# ERBB.net
KiCad netlist of a schematic drawn in Altium Designer
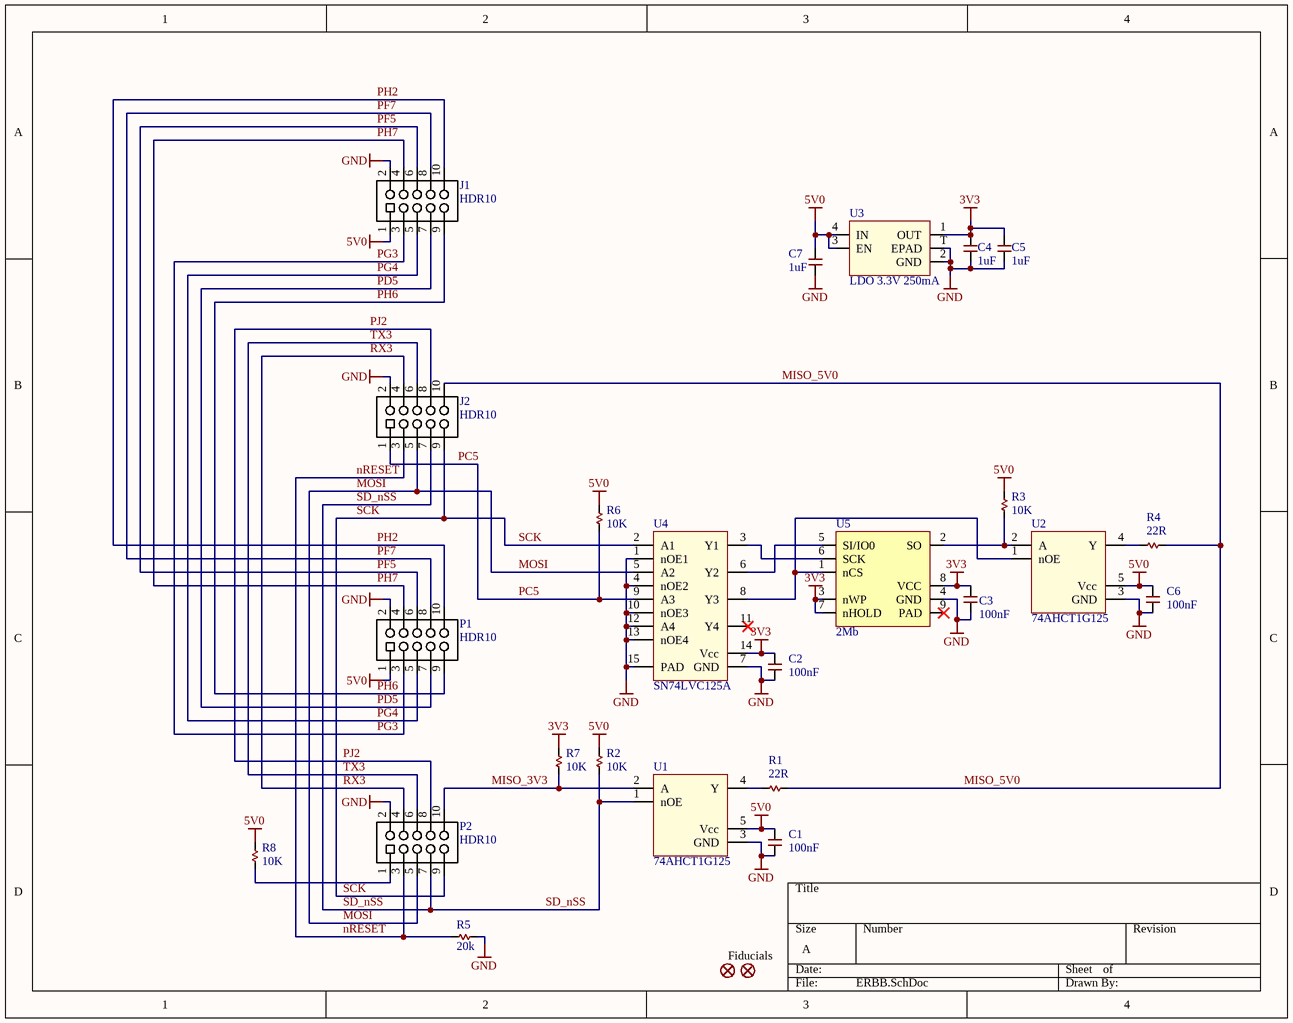
[diagram p0: ERBB.SchDoc]

(export (version "E")
  (design (tool "Eeschema 10.0.6"))
  (components
    (comp (ref "C1")
      (value "100nF")
      (footprint "C0402")
      (description "CAP CER 0402 100nF 16V 10% X7R")
      (fields (field (name "MANUFACTURER") "Murata") (field (name "PART") "0.1uF 16V X7R 0402"))
      (libsource (lib "Capacitors") (part "100nF 0402 16V X7R"))
    )
    (comp (ref "C2")
      (value "100nF")
      (footprint "C0402")
      (description "CAP CER 0402 100nF 16V 10% X7R")
      (fields (field (name "MANUFACTURER") "Murata") (field (name "PART") "0.1uF 16V X7R 0402"))
      (libsource (lib "Capacitors") (part "100nF 0402 16V X7R"))
    )
    (comp (ref "C3")
      (value "100nF")
      (footprint "C0402")
      (description "CAP CER 0402 100nF 16V 10% X7R")
      (fields (field (name "MANUFACTURER") "Murata") (field (name "PART") "0.1uF 16V X7R 0402"))
      (libsource (lib "Capacitors") (part "100nF 0402 16V X7R"))
    )
    (comp (ref "C4")
      (value "1uF")
      (footprint "C0402")
      (description "CAP CER 0402 1uF 6.3V 10% X5R")
      (fields (field (name "MANUFACTURER") "Murata") (field (name "PART") "1uF 6.3V X5R 0402"))
      (libsource (lib "Capacitors") (part "1uF 0402 6.3V X5R"))
    )
    (comp (ref "C5")
      (value "1uF")
      (footprint "C0402")
      (description "CAP CER 0402 1uF 6.3V 10% X5R")
      (fields (field (name "MANUFACTURER") "Murata") (field (name "PART") "1uF 6.3V X5R 0402"))
      (libsource (lib "Capacitors") (part "1uF 0402 6.3V X5R"))
    )
    (comp (ref "C6")
      (value "100nF")
      (footprint "C0402")
      (description "CAP CER 0402 100nF 16V 10% X7R")
      (fields (field (name "MANUFACTURER") "Murata") (field (name "PART") "0.1uF 16V X7R 0402"))
      (libsource (lib "Capacitors") (part "100nF 0402 16V X7R"))
    )
    (comp (ref "C7")
      (value "1uF")
      (footprint "C0402")
      (description "CAP CER 0402 1uF 6.3V 10% X5R")
      (fields (field (name "MANUFACTURER") "Murata") (field (name "PART") "1uF 6.3V X5R 0402"))
      (libsource (lib "Capacitors") (part "1uF 0402 6.3V X5R"))
    )
    (comp (ref "FID1")
      (value "FIDUCIAL")
      (footprint "FIDUCIAL-1X2")
      (description "Fiducial")
      (libsource (lib "3Delight") (part "FIDUCIAL"))
    )
    (comp (ref "FID2")
      (value "FIDUCIAL")
      (footprint "FIDUCIAL-1X2")
      (description "Fiducial")
      (libsource (lib "3Delight") (part "FIDUCIAL"))
    )
    (comp (ref "J1")
      (value "HDR10")
      (footprint "HDR2X5_PLUG")
      (description "CONN FM HEADER VERT 10POS GOLD")
      (fields (field (name "MANUFACTURER") "Multicomp") (field (name "TOLERANCE") "-NA-"))
      (libsource (lib "Connectors") (part "Header FM 10PIN 2ROW T-HOLE VERT"))
    )
    (comp (ref "J2")
      (value "HDR10")
      (footprint "HDR2X5_PLUG")
      (description "CONN FM HEADER VERT 10POS GOLD")
      (fields (field (name "MANUFACTURER") "Multicomp") (field (name "TOLERANCE") "-NA-"))
      (libsource (lib "Connectors") (part "Header FM 10PIN 2ROW T-HOLE VERT"))
    )
    (comp (ref "P1")
      (value "HDR10")
      (footprint "HDR2X5 IDC")
      (description "CONN HEADER VERT 10POS GOLD")
      (fields (field (name "MANUFACTURER") "On Shore") (field (name "TOLERANCE") "-NA-"))
      (libsource (lib "Connectors") (part "Header 10PIN 2ROW T-HOLE VERT SHROUDED"))
    )
    (comp (ref "P2")
      (value "HDR10")
      (footprint "HDR2X5 IDC")
      (description "CONN HEADER VERT 10POS GOLD")
      (fields (field (name "MANUFACTURER") "On Shore") (field (name "TOLERANCE") "-NA-"))
      (libsource (lib "Connectors") (part "Header 10PIN 2ROW T-HOLE VERT SHROUDED"))
    )
    (comp (ref "R1")
      (value "22R")
      (footprint "R0402")
      (description "RES 0402 22r 62.5mW 1%")
      (fields (field (name "MANUFACTURER") "Yageo") (field (name "TOLERANCE") "+/- 1%"))
      (libsource (lib "Resistors") (part "22R 1% 0402"))
    )
    (comp (ref "R2")
      (value "10K")
      (footprint "R0402")
      (description "RES SMD 10K OHM 1% 1/16W 0402")
      (fields (field (name "MANUFACTURER") "Yageo") (field (name "PART") "10k 1% 0402"))
      (libsource (lib "Resistors") (part "10k 1% 0402"))
    )
    (comp (ref "R3")
      (value "10K")
      (footprint "R0402")
      (description "RES SMD 10K OHM 1% 1/16W 0402")
      (fields (field (name "MANUFACTURER") "Yageo") (field (name "PART") "10k 1% 0402"))
      (libsource (lib "Resistors") (part "10k 1% 0402"))
    )
    (comp (ref "R4")
      (value "22R")
      (footprint "R0402")
      (description "RES 0402 22r 62.5mW 1%")
      (fields (field (name "MANUFACTURER") "Yageo") (field (name "TOLERANCE") "+/- 1%"))
      (libsource (lib "Resistors") (part "22R 1% 0402"))
    )
    (comp (ref "R5")
      (value "20k")
      (footprint "R0402")
      (description "RES SMD 20K OHM 1% 1/16W 0402")
      (fields (field (name "MANUFACTURER") "Yageo") (field (name "TOLERANCE") "1%"))
      (libsource (lib "Resistors") (part "20k 1% 0402"))
    )
    (comp (ref "R6")
      (value "10K")
      (footprint "R0402")
      (description "RES SMD 10K OHM 1% 1/16W 0402")
      (fields (field (name "MANUFACTURER") "Yageo") (field (name "PART") "10k 1% 0402"))
      (libsource (lib "Resistors") (part "10k 1% 0402"))
    )
    (comp (ref "R7")
      (value "10K")
      (footprint "R0402")
      (description "RES SMD 10K OHM 1% 1/16W 0402")
      (fields (field (name "MANUFACTURER") "Yageo") (field (name "PART") "10k 1% 0402"))
      (libsource (lib "Resistors") (part "10k 1% 0402"))
    )
    (comp (ref "R8")
      (value "10K")
      (footprint "R0402")
      (description "RES SMD 10K OHM 1% 1/16W 0402")
      (fields (field (name "MANUFACTURER") "Yageo") (field (name "PART") "10k 1% 0402"))
      (libsource (lib "Resistors") (part "10k 1% 0402"))
    )
    (comp (ref "U1")
      (value "74AHCT1G125")
      (footprint "SOTFL50P160X60-5L")
      (description "IC BUS BUFF TRI-ST N-INV  SOT-553")
      (fields (field (name "TOLERANCE") "-NA-") (field (name "MANUFACTURER") "TI"))
      (libsource (lib "ICs-Logic") (part "SN74AHCT1G125DRLR"))
    )
    (comp (ref "U2")
      (value "74AHCT1G125")
      (footprint "SOTFL50P160X60-5L")
      (description "IC BUS BUFF TRI-ST N-INV  SOT-553")
      (fields (field (name "TOLERANCE") "-NA-") (field (name "MANUFACTURER") "TI"))
      (libsource (lib "ICs-Logic") (part "SN74AHCT1G125DRLR"))
    )
    (comp (ref "U3")
      (value "LDO 3.3V 250mA")
      (footprint "XDFN4 1X1")
      (description "IC REG LINEAR 3.3V 250MA 4XDFN")
      (fields (field (name "MANUFACTURER") "On Semi") (field (name "TOLERANCE") "-NA-"))
      (libsource (lib "ICs-Power") (part "LDO 3.3V 250mA"))
    )
    (comp (ref "U4")
      (value "SN74LVC125A")
      (footprint "PVQFN14_3.5X3.5")
      (description "IC BUS BUFF TRI-ST QD 14VQFN")
      (fields (field (name "TOLERANCE") "-NA-") (field (name "MANUFACTURER") "TI"))
      (libsource (lib "ICs-Logic") (part "SN74LVC125A"))
    )
    (comp (ref "U5")
      (value "2Mb")
      (footprint "USON8 2X3")
      (description "IC FLASH 2MBIT 104MHZ 8USON")
      (fields (field (name "MANUFACTURER") "Winbond") (field (name "TOLERANCE") "-NA-"))
      (libsource (lib "ICs-uC") (part "W25X20CL"))
    )
  )
  (nets
    (net (code "1") (name "/MISO_3V3") (class "Default")
      (node (ref "P2") (pin "10") (pinfunction "10_10") (pintype "passive"))
      (node (ref "R7") (pin "2") (pinfunction "2_2") (pintype "passive"))
      (node (ref "U1") (pin "2") (pinfunction "A_2") (pintype "passive"))
    )
    (net (code "2") (name "/MISO_5V0") (class "Default")
      (node (ref "J2") (pin "10") (pinfunction "10_10") (pintype "passive"))
      (node (ref "R1") (pin "2") (pinfunction "2_2") (pintype "passive"))
      (node (ref "R4") (pin "2") (pinfunction "2_2") (pintype "passive"))
    )
    (net (code "3") (name "/MOSI") (class "Default")
      (node (ref "J2") (pin "5") (pinfunction "5_5") (pintype "passive"))
      (node (ref "P2") (pin "5") (pinfunction "5_5") (pintype "passive"))
      (node (ref "U4") (pin "5") (pinfunction "A2_5") (pintype "passive"))
    )
    (net (code "4") (name "/PC5") (class "Default")
      (node (ref "J2") (pin "1") (pinfunction "1_1") (pintype "passive"))
      (node (ref "R6") (pin "2") (pinfunction "2_2") (pintype "passive"))
      (node (ref "U4") (pin "9") (pinfunction "A3_9") (pintype "passive"))
    )
    (net (code "5") (name "/PD5") (class "Default")
      (node (ref "J1") (pin "7") (pinfunction "7_7") (pintype "passive"))
      (node (ref "P1") (pin "7") (pinfunction "7_7") (pintype "passive"))
    )
    (net (code "6") (name "/PF5") (class "Default")
      (node (ref "J1") (pin "6") (pinfunction "6_6") (pintype "passive"))
      (node (ref "P1") (pin "6") (pinfunction "6_6") (pintype "passive"))
    )
    (net (code "7") (name "/PF7") (class "Default")
      (node (ref "J1") (pin "8") (pinfunction "8_8") (pintype "passive"))
      (node (ref "P1") (pin "8") (pinfunction "8_8") (pintype "passive"))
    )
    (net (code "8") (name "/PG3") (class "Default")
      (node (ref "J1") (pin "3") (pinfunction "3_3") (pintype "passive"))
      (node (ref "P1") (pin "3") (pinfunction "3_3") (pintype "passive"))
    )
    (net (code "9") (name "/PG4") (class "Default")
      (node (ref "J1") (pin "5") (pinfunction "5_5") (pintype "passive"))
      (node (ref "P1") (pin "5") (pinfunction "5_5") (pintype "passive"))
    )
    (net (code "10") (name "/PH2") (class "Default")
      (node (ref "J1") (pin "10") (pinfunction "10_10") (pintype "passive"))
      (node (ref "P1") (pin "10") (pinfunction "10_10") (pintype "passive"))
    )
    (net (code "11") (name "/PH6") (class "Default")
      (node (ref "J1") (pin "9") (pinfunction "9_9") (pintype "passive"))
      (node (ref "P1") (pin "9") (pinfunction "9_9") (pintype "passive"))
    )
    (net (code "12") (name "/PH7") (class "Default")
      (node (ref "J1") (pin "4") (pinfunction "4_4") (pintype "passive"))
      (node (ref "P1") (pin "4") (pinfunction "4_4") (pintype "passive"))
    )
    (net (code "13") (name "/PJ2") (class "Default")
      (node (ref "J2") (pin "8") (pinfunction "8_8") (pintype "passive"))
      (node (ref "P2") (pin "8") (pinfunction "8_8") (pintype "passive"))
    )
    (net (code "14") (name "/RX3") (class "Default")
      (node (ref "J2") (pin "4") (pinfunction "4_4") (pintype "passive"))
      (node (ref "P2") (pin "4") (pinfunction "4_4") (pintype "passive"))
    )
    (net (code "15") (name "/SCK") (class "Default")
      (node (ref "J2") (pin "9") (pinfunction "9_9") (pintype "passive"))
      (node (ref "P2") (pin "9") (pinfunction "9_9") (pintype "passive"))
      (node (ref "U4") (pin "2") (pinfunction "A1_2") (pintype "passive"))
    )
    (net (code "16") (name "/SD_nSS") (class "Default")
      (node (ref "J2") (pin "7") (pinfunction "7_7") (pintype "passive"))
      (node (ref "P2") (pin "7") (pinfunction "7_7") (pintype "passive"))
      (node (ref "R2") (pin "2") (pinfunction "2_2") (pintype "passive"))
      (node (ref "U1") (pin "1") (pinfunction "nOE_1") (pintype "passive"))
    )
    (net (code "17") (name "/TX3") (class "Default")
      (node (ref "J2") (pin "6") (pinfunction "6_6") (pintype "passive"))
      (node (ref "P2") (pin "6") (pinfunction "6_6") (pintype "passive"))
    )
    (net (code "18") (name "/nRESET") (class "Default")
      (node (ref "J2") (pin "3") (pinfunction "3_3") (pintype "passive"))
      (node (ref "P2") (pin "3") (pinfunction "3_3") (pintype "passive"))
      (node (ref "R5") (pin "1") (pinfunction "1_1") (pintype "passive"))
    )
    (net (code "19") (name "3V3") (class "Default")
      (node (ref "C2") (pin "1") (pinfunction "1_1") (pintype "passive"))
      (node (ref "C3") (pin "2") (pinfunction "2_2") (pintype "passive"))
      (node (ref "C4") (pin "2") (pinfunction "2_2") (pintype "passive"))
      (node (ref "C5") (pin "2") (pinfunction "2_2") (pintype "passive"))
      (node (ref "R7") (pin "1") (pinfunction "1_1") (pintype "passive"))
      (node (ref "U3") (pin "1") (pinfunction "OUT_1") (pintype "power_in"))
      (node (ref "U4") (pin "14") (pinfunction "Vcc_14") (pintype "passive"))
      (node (ref "U5") (pin "3") (pinfunction "nWP_3") (pintype "passive"))
      (node (ref "U5") (pin "7") (pinfunction "nHOLD_7") (pintype "passive"))
      (node (ref "U5") (pin "8") (pinfunction "VCC_8") (pintype "passive"))
    )
    (net (code "20") (name "5V0") (class "Default")
      (node (ref "C1") (pin "2") (pinfunction "2_2") (pintype "passive"))
      (node (ref "C6") (pin "2") (pinfunction "2_2") (pintype "passive"))
      (node (ref "C7") (pin "2") (pinfunction "2_2") (pintype "passive"))
      (node (ref "J1") (pin "1") (pinfunction "1_1") (pintype "passive"))
      (node (ref "P1") (pin "1") (pinfunction "1_1") (pintype "passive"))
      (node (ref "R2") (pin "1") (pinfunction "1_1") (pintype "passive"))
      (node (ref "R3") (pin "1") (pinfunction "1_1") (pintype "passive"))
      (node (ref "R6") (pin "1") (pinfunction "1_1") (pintype "passive"))
      (node (ref "R8") (pin "1") (pinfunction "1_1") (pintype "passive"))
      (node (ref "U1") (pin "5") (pinfunction "Vcc_5") (pintype "passive"))
      (node (ref "U2") (pin "5") (pinfunction "Vcc_5") (pintype "passive"))
      (node (ref "U3") (pin "3") (pinfunction "EN_3") (pintype "power_in"))
      (node (ref "U3") (pin "4") (pinfunction "IN_4") (pintype "power_in"))
    )
    (net (code "21") (name "GND") (class "Default")
      (node (ref "C1") (pin "1") (pinfunction "1_1") (pintype "passive"))
      (node (ref "C2") (pin "2") (pinfunction "2_2") (pintype "passive"))
      (node (ref "C3") (pin "1") (pinfunction "1_1") (pintype "passive"))
      (node (ref "C4") (pin "1") (pinfunction "1_1") (pintype "passive"))
      (node (ref "C5") (pin "1") (pinfunction "1_1") (pintype "passive"))
      (node (ref "C6") (pin "1") (pinfunction "1_1") (pintype "passive"))
      (node (ref "C7") (pin "1") (pinfunction "1_1") (pintype "passive"))
      (node (ref "J1") (pin "2") (pinfunction "2_2") (pintype "passive"))
      (node (ref "J2") (pin "2") (pinfunction "2_2") (pintype "passive"))
      (node (ref "P1") (pin "2") (pinfunction "2_2") (pintype "passive"))
      (node (ref "P2") (pin "2") (pinfunction "2_2") (pintype "passive"))
      (node (ref "R5") (pin "2") (pinfunction "2_2") (pintype "passive"))
      (node (ref "U1") (pin "3") (pinfunction "GND_3") (pintype "passive"))
      (node (ref "U2") (pin "3") (pinfunction "GND_3") (pintype "passive"))
      (node (ref "U3") (pin "2") (pinfunction "GND_2") (pintype "power_in"))
      (node (ref "U3") (pin "T") (pinfunction "EPAD_T") (pintype "power_in"))
      (node (ref "U4") (pin "1") (pinfunction "nOE1_1") (pintype "passive"))
      (node (ref "U4") (pin "10") (pinfunction "nOE3_10") (pintype "passive"))
      (node (ref "U4") (pin "12") (pinfunction "A4_12") (pintype "passive"))
      (node (ref "U4") (pin "13") (pinfunction "nOE4_13") (pintype "passive"))
      (node (ref "U4") (pin "15") (pinfunction "PAD_15") (pintype "passive"))
      (node (ref "U4") (pin "4") (pinfunction "nOE2_4") (pintype "passive"))
      (node (ref "U4") (pin "7") (pinfunction "GND_7") (pintype "passive"))
      (node (ref "U5") (pin "4") (pinfunction "GND_4") (pintype "passive"))
    )
    (net (code "22") (name "Net-(P2-Pad1)") (class "Default")
      (node (ref "P2") (pin "1") (pinfunction "1_1") (pintype "passive"))
      (node (ref "R8") (pin "2") (pinfunction "2_2") (pintype "passive"))
    )
    (net (code "23") (name "Net-(U1-Y)") (class "Default")
      (node (ref "R1") (pin "1") (pinfunction "1_1") (pintype "passive"))
      (node (ref "U1") (pin "4") (pinfunction "Y_4") (pintype "passive"))
    )
    (net (code "24") (name "Net-(U2-A)") (class "Default")
      (node (ref "R3") (pin "2") (pinfunction "2_2") (pintype "passive"))
      (node (ref "U2") (pin "2") (pinfunction "A_2") (pintype "passive"))
      (node (ref "U5") (pin "2") (pinfunction "SO_2") (pintype "passive"))
    )
    (net (code "25") (name "Net-(U2-Y)") (class "Default")
      (node (ref "R4") (pin "1") (pinfunction "1_1") (pintype "passive"))
      (node (ref "U2") (pin "4") (pinfunction "Y_4") (pintype "passive"))
    )
    (net (code "26") (name "Net-(U2-nOE)") (class "Default")
      (node (ref "U2") (pin "1") (pinfunction "nOE_1") (pintype "passive"))
      (node (ref "U4") (pin "8") (pinfunction "Y3_8") (pintype "passive"))
      (node (ref "U5") (pin "1") (pinfunction "nCS_1") (pintype "passive"))
    )
    (net (code "27") (name "Net-(U4-Y1)") (class "Default")
      (node (ref "U4") (pin "3") (pinfunction "Y1_3") (pintype "passive"))
      (node (ref "U5") (pin "6") (pinfunction "SCK_6") (pintype "passive"))
    )
    (net (code "28") (name "Net-(U4-Y2)") (class "Default")
      (node (ref "U4") (pin "6") (pinfunction "Y2_6") (pintype "passive"))
      (node (ref "U5") (pin "5") (pinfunction "SI/IO0_5") (pintype "passive"))
    )
    (net (code "29") (name "unconnected-(U1-NC-Pad23)") (class "Default")
      (node (ref "U1") (pin "23") (pinfunction "NC_23") (pintype "passive"))
    )
    (net (code "30") (name "unconnected-(U2-NC-Pad23)") (class "Default")
      (node (ref "U2") (pin "23") (pinfunction "NC_23") (pintype "passive"))
    )
    (net (code "31") (name "unconnected-(U4-NC-Pad23)") (class "Default")
      (node (ref "U4") (pin "23") (pinfunction "NC_23") (pintype "passive"))
    )
    (net (code "32") (name "unconnected-(U4-Y4-Pad11)") (class "Default")
      (node (ref "U4") (pin "11") (pinfunction "Y4_11") (pintype "passive+no_connect"))
    )
    (net (code "33") (name "unconnected-(U5-PAD-Pad9)") (class "Default")
      (node (ref "U5") (pin "9") (pinfunction "PAD_9") (pintype "passive+no_connect"))
    )
  )
)
